# design.net
KiCad netlist of a schematic drawn in Altium Designer
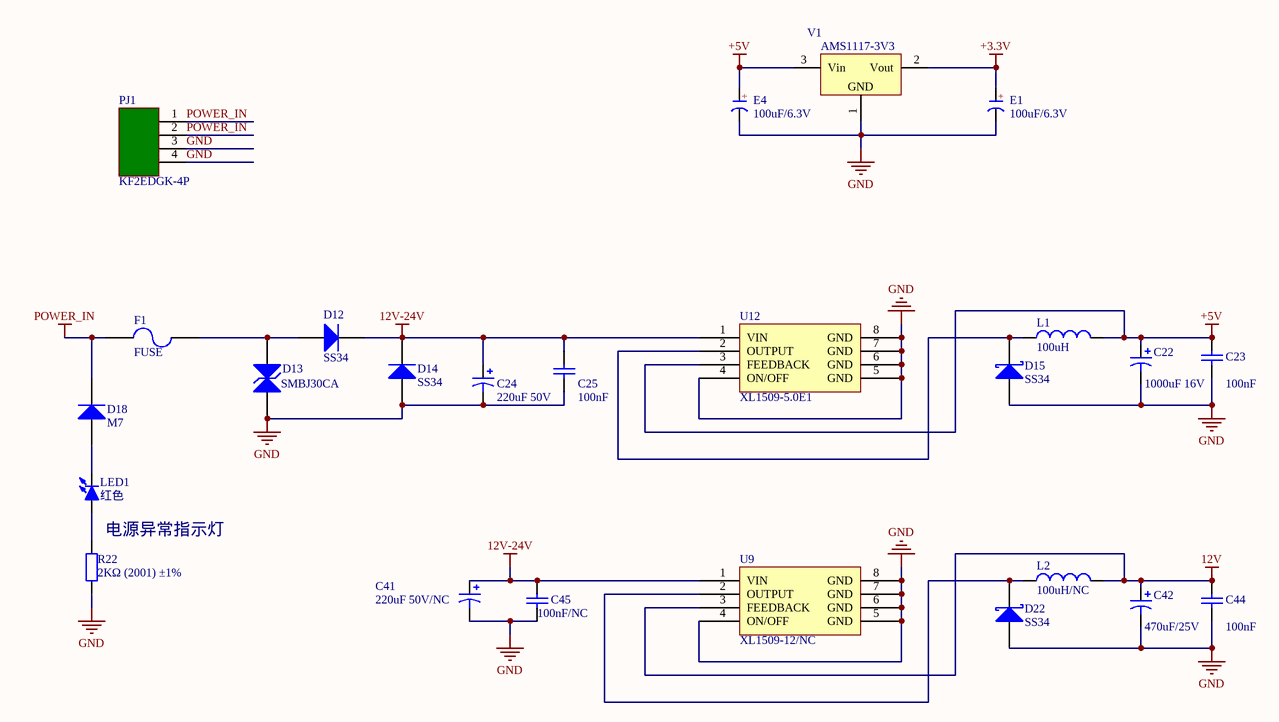
[diagram p0: 电源.SchDoc]

(export (version "E")
  (design (tool "Eeschema 10.0.6"))
  (components
    (comp (ref "C22")
      (value "1000uF 16V")
      (footprint "CAP 5.0*10*12.5")
      (description "Polarized Capacitor (Radial)")
      (fields (field (name "Comment") "Cap Pol1") (field (name "PUBLISHER") "Altium Limited"))
      (libsource (lib "Miscellaneous Devices") (part "Cap Pol1"))
    )
    (comp (ref "C23")
      (value "100nF")
      (footprint "1206_c")
      (description "Capacitor (Semiconductor SIM Model)")
      (fields (field (name "Comment") "Cap Semi") (field (name "PUBLISHER") "Altium Limited"))
      (libsource (lib "Miscellaneous Devices") (part "Cap Semi"))
    )
    (comp (ref "C24")
      (value "220uF 50V")
      (footprint "CAP 5.0*10*12.5")
      (description "Polarized Capacitor (Radial)")
      (fields (field (name "Comment") "Cap Pol1") (field (name "PUBLISHER") "Altium Limited"))
      (libsource (lib "Miscellaneous Devices") (part "Cap Pol1"))
    )
    (comp (ref "C25")
      (value "100nF")
      (footprint "1206_c")
      (description "贴片电容")
      (libsource (lib "Miscellaneous Devices LC") (part "0603 100nF (104) 10% 50V"))
    )
    (comp (ref "C41")
      (value "220uF 50V/NC")
      (footprint "CAP 5.0*10*12.5")
      (description "Polarized Capacitor (Radial)")
      (fields (field (name "Comment") "Cap Pol1") (field (name "PUBLISHER") "Altium Limited"))
      (libsource (lib "Miscellaneous Devices") (part "Cap Pol1"))
    )
    (comp (ref "C42")
      (value "470uF/25V")
      (footprint "CAP 5.0*10*12.5")
      (description "Polarized Capacitor (Radial)")
      (fields (field (name "Comment") "Cap Pol1") (field (name "PUBLISHER") "Altium Limited"))
      (libsource (lib "Miscellaneous Devices") (part "Cap Pol1"))
    )
    (comp (ref "C44")
      (value "100nF")
      (footprint "1206_c")
      (description "Capacitor (Semiconductor SIM Model)")
      (fields (field (name "Comment") "Cap Semi") (field (name "PUBLISHER") "Altium Limited"))
      (libsource (lib "Miscellaneous Devices") (part "Cap Semi"))
    )
    (comp (ref "C45")
      (value "100nF/NC")
      (footprint "1206_c")
      (description "贴片电容")
      (libsource (lib "Miscellaneous Devices LC") (part "0603 100nF (104) 10% 50V"))
    )
    (comp (ref "D12")
      (value "SS34")
      (footprint "SMA(DO-214AC)_S1")
      (description "二极管")
      (libsource (lib "Miscellaneous Devices LC") (part "SMA(DO-214AC) SS54"))
    )
    (comp (ref "D13")
      (value "SMBJ30CA")
      (footprint "SMB(DO-214AA)_S1")
      (description "TVS")
      (libsource (lib "Miscellaneous Devices LC") (part "SMB/DO-214AA P6SMB6.8CA"))
    )
    (comp (ref "D14")
      (value "SS34")
      (footprint "SMA(DO-214AC)_S1")
      (description "二极管")
      (libsource (lib "Miscellaneous Devices LC") (part "SMA(DO-214AC) SS54"))
    )
    (comp (ref "D15")
      (value "SS34")
      (footprint "SMA(DO-214AC)_S1")
      (description "Schottky Diode")
      (fields (field (name "PUBLISHER") "Altium Limited"))
      (libsource (lib "Miscellaneous Devices") (part "D Schottky"))
    )
    (comp (ref "D18")
      (value "M7")
      (footprint "SMA(DO-214AC)_S1")
      (description "二极管")
      (libsource (lib "Miscellaneous Devices LC") (part "SMA(DO-214AC) M7"))
    )
    (comp (ref "D22")
      (value "SS34")
      (footprint "SMA(DO-214AC)_S1")
      (description "Schottky Diode")
      (fields (field (name "PUBLISHER") "Altium Limited"))
      (libsource (lib "Miscellaneous Devices") (part "D Schottky"))
    )
    (comp (ref "E1")
      (value "100uF/6.3V")
      (footprint "CM C(5*5.4)")
      (description "贴片电解电容")
      (fields (field (name "版权归属") "源创客"))
      (libsource (lib "源创客") (part "C-CM"))
    )
    (comp (ref "E4")
      (value "100uF/6.3V")
      (footprint "CM C(5*5.4)")
      (description "贴片电解电容")
      (fields (field (name "版权归属") "源创客"))
      (libsource (lib "源创客") (part "C-CM"))
    )
    (comp (ref "F1") (value "FUSE") (footprint "FUSE-RAD0.2") (libsource (lib "保险丝") (part "FUSE")))
    (comp (ref "L1")
      (value "100uH")
      (footprint "CD75")
      (description "Inductor")
      (fields (field (name "PUBLISHER") "Altium Limited"))
      (libsource (lib "Miscellaneous Devices") (part "Inductor"))
    )
    (comp (ref "L2")
      (value "100uH/NC")
      (footprint "CD75")
      (description "Inductor")
      (fields (field (name "PUBLISHER") "Altium Limited"))
      (libsource (lib "Miscellaneous Devices") (part "Inductor"))
    )
    (comp (ref "LED1")
      (value "红色")
      (footprint "LED 1206R")
      (description "贴片LED")
      (fields (field (name "版权归属") "源创客"))
      (libsource (lib "源创客") (part "LED-SMD"))
    )
    (comp (ref "PJ1")
      (value "KF2EDGK-4P")
      (footprint "KF2EDGK5.08W-4P")
      (libsource (lib "KF2EDGK") (part "KF2EDGK-4P"))
    )
    (comp (ref "R22")
      (value "2KΩ (2001) ±1%")
      (footprint "1206_R")
      (description "贴片电阻")
      (libsource (lib "Miscellaneous Devices LC") (part "1206 2KΩ (2001) 1%"))
    )
    (comp (ref "U9")
      (value "XL1509-12/NC")
      (footprint "SOP-8_150mil")
      (description "DC-DC芯片")
      (libsource (lib "Miscellaneous Devices LC") (part "XL1509-5.0E1"))
    )
    (comp (ref "U12")
      (value "XL1509-5.0E1")
      (footprint "SOP-8_150mil")
      (description "DC-DC芯片")
      (libsource (lib "Miscellaneous Devices LC") (part "XL1509-5.0E1"))
    )
    (comp (ref "V1")
      (value "AMS1117-3V3")
      (footprint "SOT223_L")
      (description "三端稳压芯片")
      (fields (field (name "版权归属") "源创客"))
      (libsource (lib "源创客") (part "AMS1117"))
    )
  )
  (nets
    (net (code "1") (name "+3.3V") (class "Default")
      (node (ref "E1") (pin "1") (pinfunction "A_1") (pintype "passive"))
      (node (ref "V1") (pin "2") (pinfunction "Vout_2") (pintype "passive"))
    )
    (net (code "2") (name "+5V") (class "Default")
      (node (ref "C22") (pin "1") (pinfunction "1_1") (pintype "passive"))
      (node (ref "C23") (pin "2") (pinfunction "2_2") (pintype "passive"))
      (node (ref "E4") (pin "1") (pinfunction "A_1") (pintype "passive"))
      (node (ref "L1") (pin "2") (pinfunction "2_2") (pintype "passive"))
      (node (ref "U12") (pin "3") (pinfunction "FEEDBACK_3") (pintype "passive"))
      (node (ref "V1") (pin "3") (pinfunction "Vin_3") (pintype "passive"))
    )
    (net (code "3") (name "12V") (class "Default")
      (node (ref "C42") (pin "1") (pinfunction "1_1") (pintype "passive"))
      (node (ref "C44") (pin "2") (pinfunction "2_2") (pintype "passive"))
      (node (ref "L2") (pin "2") (pinfunction "2_2") (pintype "passive"))
      (node (ref "U9") (pin "3") (pinfunction "FEEDBACK_3") (pintype "passive"))
    )
    (net (code "4") (name "12V-24V") (class "Default")
      (node (ref "C24") (pin "1") (pinfunction "1_1") (pintype "passive"))
      (node (ref "C25") (pin "2") (pinfunction "2_2") (pintype "passive"))
      (node (ref "C41") (pin "1") (pinfunction "1_1") (pintype "passive"))
      (node (ref "C45") (pin "2") (pinfunction "2_2") (pintype "passive"))
      (node (ref "D12") (pin "2") (pinfunction "K_2") (pintype "passive"))
      (node (ref "D14") (pin "2") (pinfunction "K_2") (pintype "passive"))
      (node (ref "U12") (pin "1") (pinfunction "VIN_1") (pintype "passive"))
      (node (ref "U9") (pin "1") (pinfunction "VIN_1") (pintype "passive"))
    )
    (net (code "5") (name "GND") (class "Default")
      (node (ref "C22") (pin "2") (pinfunction "2_2") (pintype "passive"))
      (node (ref "C23") (pin "1") (pinfunction "1_1") (pintype "passive"))
      (node (ref "C24") (pin "2") (pinfunction "2_2") (pintype "passive"))
      (node (ref "C25") (pin "1") (pinfunction "1_1") (pintype "passive"))
      (node (ref "C41") (pin "2") (pinfunction "2_2") (pintype "passive"))
      (node (ref "C42") (pin "2") (pinfunction "2_2") (pintype "passive"))
      (node (ref "C44") (pin "1") (pinfunction "1_1") (pintype "passive"))
      (node (ref "C45") (pin "1") (pinfunction "1_1") (pintype "passive"))
      (node (ref "D13") (pin "1") (pinfunction "A_1") (pintype "passive"))
      (node (ref "D14") (pin "1") (pinfunction "A_1") (pintype "passive"))
      (node (ref "D15") (pin "1") (pinfunction "A_1") (pintype "passive"))
      (node (ref "D22") (pin "1") (pinfunction "A_1") (pintype "passive"))
      (node (ref "E1") (pin "2") (pinfunction "K_2") (pintype "passive"))
      (node (ref "E4") (pin "2") (pinfunction "K_2") (pintype "passive"))
      (node (ref "PJ1") (pin "3") (pinfunction "3_3") (pintype "passive"))
      (node (ref "PJ1") (pin "4") (pinfunction "4_4") (pintype "passive"))
      (node (ref "R22") (pin "1") (pinfunction "1_1") (pintype "passive"))
      (node (ref "U12") (pin "4") (pinfunction "ON/OFF_4") (pintype "passive"))
      (node (ref "U12") (pin "5") (pinfunction "GND_5") (pintype "passive"))
      (node (ref "U12") (pin "6") (pinfunction "GND_6") (pintype "passive"))
      (node (ref "U12") (pin "7") (pinfunction "GND_7") (pintype "passive"))
      (node (ref "U12") (pin "8") (pinfunction "GND_8") (pintype "passive"))
      (node (ref "U9") (pin "4") (pinfunction "ON/OFF_4") (pintype "passive"))
      (node (ref "U9") (pin "5") (pinfunction "GND_5") (pintype "passive"))
      (node (ref "U9") (pin "6") (pinfunction "GND_6") (pintype "passive"))
      (node (ref "U9") (pin "7") (pinfunction "GND_7") (pintype "passive"))
      (node (ref "U9") (pin "8") (pinfunction "GND_8") (pintype "passive"))
      (node (ref "V1") (pin "1") (pinfunction "GND_1") (pintype "passive"))
    )
    (net (code "6") (name "Net-(D12-A)") (class "Default")
      (node (ref "D12") (pin "1") (pinfunction "A_1") (pintype "passive"))
      (node (ref "D13") (pin "2") (pinfunction "K_2") (pintype "passive"))
      (node (ref "F1") (pin "2") (pinfunction "2_2") (pintype "passive"))
    )
    (net (code "7") (name "Net-(D15-K)") (class "Default")
      (node (ref "D15") (pin "2") (pinfunction "K_2") (pintype "passive"))
      (node (ref "L1") (pin "1") (pinfunction "1_1") (pintype "passive"))
      (node (ref "U12") (pin "2") (pinfunction "OUTPUT_2") (pintype "passive"))
    )
    (net (code "8") (name "Net-(D18-A)") (class "Default")
      (node (ref "D18") (pin "1") (pinfunction "A_1") (pintype "passive"))
      (node (ref "LED1") (pin "2") (pinfunction "K_2") (pintype "passive"))
    )
    (net (code "9") (name "Net-(D22-K)") (class "Default")
      (node (ref "D22") (pin "2") (pinfunction "K_2") (pintype "passive"))
      (node (ref "L2") (pin "1") (pinfunction "1_1") (pintype "passive"))
      (node (ref "U9") (pin "2") (pinfunction "OUTPUT_2") (pintype "passive"))
    )
    (net (code "10") (name "Net-(LED1-A)") (class "Default")
      (node (ref "LED1") (pin "1") (pinfunction "A_1") (pintype "passive"))
      (node (ref "R22") (pin "2") (pinfunction "2_2") (pintype "passive"))
    )
    (net (code "11") (name "POWER_IN") (class "Default")
      (node (ref "D18") (pin "2") (pinfunction "K_2") (pintype "passive"))
      (node (ref "F1") (pin "1") (pinfunction "1_1") (pintype "passive"))
      (node (ref "PJ1") (pin "1") (pinfunction "1_1") (pintype "passive"))
      (node (ref "PJ1") (pin "2") (pinfunction "2_2") (pintype "passive"))
    )
  )
)
